# Power_Supply.net
KiCad netlist of a schematic drawn in Altium Designer
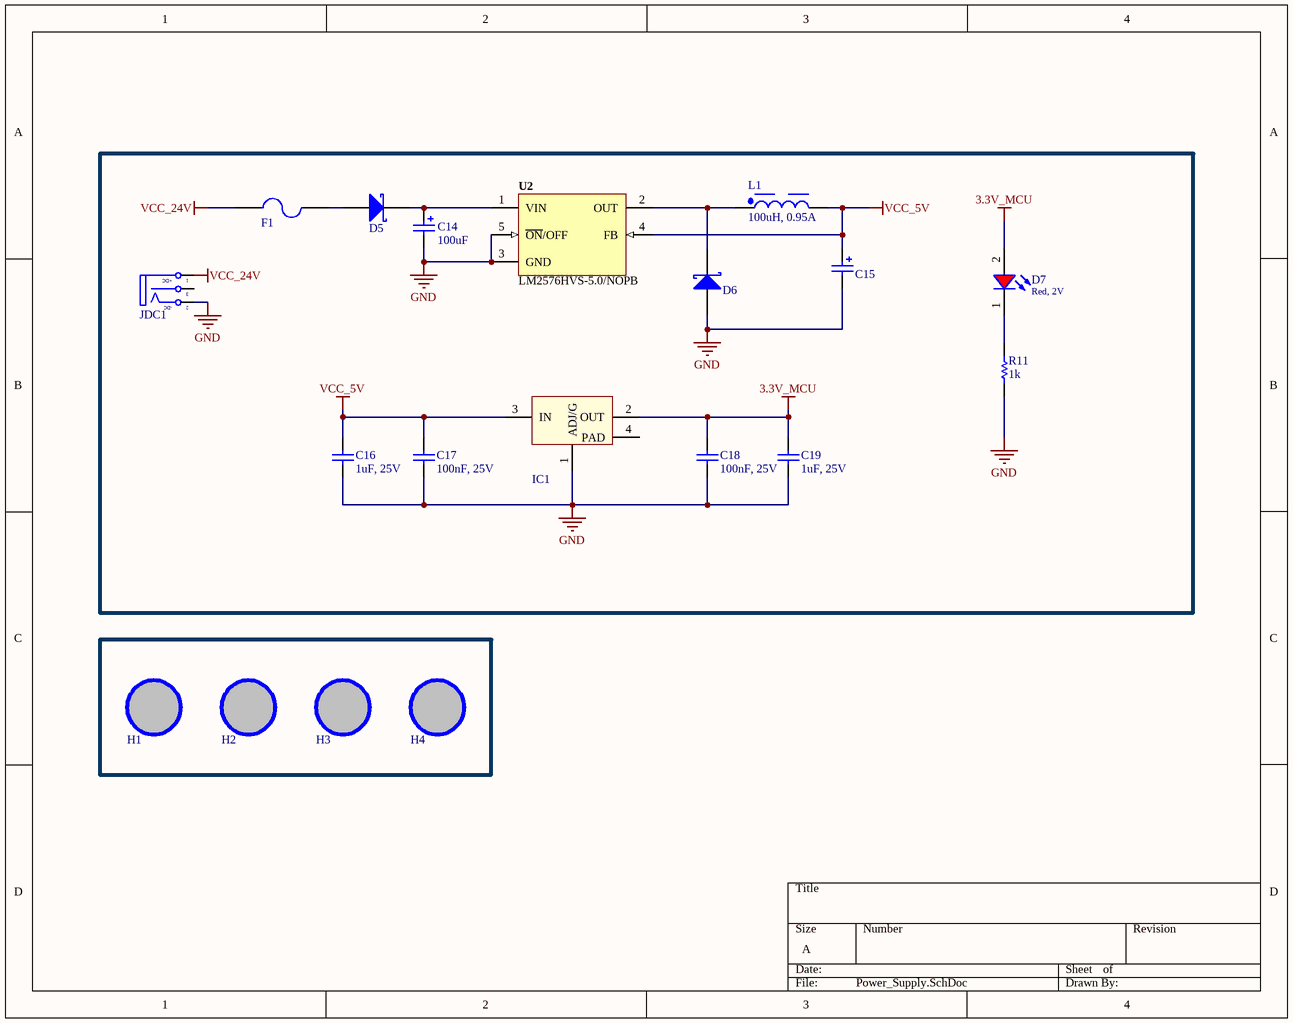
[diagram p0: Power_Supply.SchDoc]

(export (version "E")
  (design (tool "Eeschema 10.0.6"))
  (components
    (comp (ref "C14")
      (value "100uF")
      (footprint "WCAP-ATG8_D8H11.5")
      (description "WCAP-ATG8 Aluminum Electrolytic Capacitor, Radial THT, D8xH11.5mm, 100uF, 50V")
      (fields
        (field (name "MANUFACTURER") "Wurth Elektronik")
        (field (name "MANUFACTURER PART NUMBER") "860010674014")
      )
      (libsource (lib "Altium_WCAP-ATG8 (rev22a)") (part "860010674014"))
    )
    (comp (ref "C15")
      (value "1000uF")
      (footprint "WCAP-ATG8_D13H25")
      (description "WCAP-ATG8 Aluminum Electrolytic Capacitor, Radial THT, D13xH25mm, 1000uF, 50V")
      (fields
        (field (name "MANUFACTURER") "Wurth Elektronik")
        (field (name "MANUFACTURER PART NUMBER") "860010678024")
      )
      (libsource (lib "Altium_WCAP-ATG8 (rev22a)") (part "860010678024"))
    )
    (comp (ref "C16")
      (value "1uF, 25V")
      (footprint "WCAP-CSGP_0603_H=0.8mm_Reflow")
      (description "WCAP-CSGP Multilayer Ceramic Chip Capacitor, General Purpose, size 0603, X5R, 1uF, 25V")
      (fields
        (field (name "MANUFACTURER PART NUMBER") "885012106022")
        (field (name "MANUFACTURER") "Wurth Elektronik")
      )
      (libsource (lib "Altium_WCAP-CSGP (rev20a)") (part "885012106022"))
    )
    (comp (ref "C17")
      (value "100nF, 25V")
      (footprint "WCAP-CSGP_0603_H=0.8mm_Reflow")
      (description "WCAP-CSGP Multilayer Ceramic Chip Capacitor, General Purpose, size 0603, X7R, 100nF, 25V")
      (fields
        (field (name "MANUFACTURER PART NUMBER") "885012206071")
        (field (name "MANUFACTURER") "Wurth Elektronik")
      )
      (libsource (lib "Altium_WCAP-CSGP (rev20a)") (part "885012206071"))
    )
    (comp (ref "C18")
      (value "100nF, 25V")
      (footprint "WCAP-CSGP_0603_H=0.8mm_Reflow")
      (description "WCAP-CSGP Multilayer Ceramic Chip Capacitor, General Purpose, size 0603, X7R, 100nF, 25V")
      (fields
        (field (name "MANUFACTURER PART NUMBER") "885012206071")
        (field (name "MANUFACTURER") "Wurth Elektronik")
      )
      (libsource (lib "Altium_WCAP-CSGP (rev20a)") (part "885012206071"))
    )
    (comp (ref "C19")
      (value "1uF, 25V")
      (footprint "WCAP-CSGP_0603_H=0.8mm_Reflow")
      (description "WCAP-CSGP Multilayer Ceramic Chip Capacitor, General Purpose, size 0603, X5R, 1uF, 25V")
      (fields
        (field (name "MANUFACTURER PART NUMBER") "885012106022")
        (field (name "MANUFACTURER") "Wurth Elektronik")
      )
      (libsource (lib "Altium_WCAP-CSGP (rev20a)") (part "885012106022"))
    )
    (comp (ref "D5")
      (value "SS34")
      (footprint "SS34")
      (description "DIODE SCHOTTKY 40V 3A SMC")
      (fields (field (name "MFR") "onsemi") (field (name "PUBLISHER") "Altium Limited"))
      (libsource (lib "PIF_Library") (part "D Schottky"))
    )
    (comp (ref "D6")
      (value "SS34")
      (footprint "SS34")
      (description "DIODE SCHOTTKY 40V 3A SMC")
      (fields (field (name "MFR") "onsemi") (field (name "PUBLISHER") "Altium Limited"))
      (libsource (lib "PIF_Library") (part "D Schottky"))
    )
    (comp (ref "D7")
      (value "Red, 2V")
      (footprint "WL-SMCW_0603_H=0.7mm")
      (description "WL-SMCW SMT Mono-color Chip LED Waterclear, size 0603, Red, 2V, 140deg")
      (fields (field (name "PART NUMBER") "150060RS75000") (field (name "PUBLISHER") "Wurth Elektronik"))
      (libsource (lib "Altium_WL-SMCW (rev20a)") (part "150060RS75000"))
    )
    (comp (ref "F1")
      (value "0ZCG0150BF2C")
      (footprint "FUSE SMD")
      (description "PTC RESET FUSE 24V 1.5A 1812")
      (fields (field (name "MFR") "Bel Fuse Inc."))
      (libsource (lib "PIF_Library") (part "Fuse"))
    )
    (comp (ref "H1")
      (value "Hole")
      (footprint "LO KHOAN 3MM")
      (description "Hole 3mm")
      (libsource (lib "PIF_Library") (part "Hole"))
    )
    (comp (ref "H2")
      (value "Hole")
      (footprint "LO KHOAN 3MM")
      (description "Hole 3mm")
      (libsource (lib "PIF_Library") (part "Hole"))
    )
    (comp (ref "H3")
      (value "Hole")
      (footprint "LO KHOAN 3MM")
      (description "Hole 3mm")
      (libsource (lib "PIF_Library") (part "Hole"))
    )
    (comp (ref "H4")
      (value "Hole")
      (footprint "LO KHOAN 3MM")
      (description "Hole 3mm")
      (libsource (lib "PIF_Library") (part "Hole"))
    )
    (comp (ref "IC1")
      (value "LM1117IMP-3.3/NOPB")
      (footprint "SOT223-4N")
      (description "IC REG LINEAR 3.3V 800MA SOT223")
      (fields (field (name "MFR") "Texas Instruments"))
      (libsource (lib "PIF_Library") (part "LM1117"))
    )
    (comp (ref "JDC1")
      (value "G-014-4")
      (footprint "DC-IN")
      (description "DC POWER JACK, MATES TO 5.5 X 2.")
      (fields (field (name "MFR") "GlobTek, Inc."))
      (libsource (lib "PIF_Library") (part "Jack DC"))
    )
    (comp (ref "L1")
      (value "100uH, 0.95A")
      (footprint "WE-PD2SR_7850")
      (description "WE-PD2SR SMT Power Inductor, size 7850, 100uH, 0.95A, 467mOhm")
      (fields
        (field (name "MANUFACTURER") "Wurth Elektronik")
        (field (name "MANUFACTURER PART NUMBER") "744787101")
      )
      (libsource (lib "WE-PD2SR (rev22a)") (part "744787101"))
    )
    (comp (ref "R11")
      (value "1k")
      (footprint "RES-SM-0603")
      (description "RES SMD 1K OHM 5% 1/4W 0603")
      (fields (field (name "MFR") "Rohm Semiconductor") (field (name "TOLERANCE") "±5%"))
      (libsource (lib "PIF_Library") (part "RESISTOR SMD"))
    )
    (comp (ref "U2")
      (value "LM2576HVS-5.0/NOPB")
      (footprint "TO263")
      (description "IC REG BUCK 5V 3A TO263-5")
      (libsource (lib "TechMT.VN_Lib_Project v2") (part "LM2576"))
    )
  )
  (nets
    (net (code "1") (name "3.3V_MCU") (class "Default")
      (node (ref "C18") (pin "2") (pinfunction "2_2") (pintype "passive"))
      (node (ref "C19") (pin "2") (pinfunction "2_2") (pintype "passive"))
      (node (ref "D7") (pin "2") (pinfunction "A_2") (pintype "passive"))
      (node (ref "IC1") (pin "2") (pinfunction "OUT_2") (pintype "passive"))
    )
    (net (code "2") (name "GND") (class "Default")
      (node (ref "C14") (pin "2") (pinfunction "N_2") (pintype "passive"))
      (node (ref "C15") (pin "2") (pinfunction "N_2") (pintype "passive"))
      (node (ref "C16") (pin "2") (pinfunction "2_2") (pintype "passive"))
      (node (ref "C17") (pin "1") (pinfunction "1_1") (pintype "passive"))
      (node (ref "C18") (pin "1") (pinfunction "1_1") (pintype "passive"))
      (node (ref "C19") (pin "1") (pinfunction "1_1") (pintype "passive"))
      (node (ref "D6") (pin "1") (pinfunction "A_1") (pintype "passive"))
      (node (ref "IC1") (pin "1") (pinfunction "ADJ/G_1") (pintype "passive"))
      (node (ref "JDC1") (pin "2") (pinfunction "TN_2") (pintype "passive"))
      (node (ref "R11") (pin "1") (pinfunction "1_1") (pintype "passive"))
      (node (ref "U2") (pin "3") (pinfunction "GND_3") (pintype "power_in"))
      (node (ref "U2") (pin "5") (pinfunction "~{ON}/OFF_5") (pintype "input"))
    )
    (net (code "3") (name "Net-(C14-P)") (class "Default")
      (node (ref "C14") (pin "1") (pinfunction "P_1") (pintype "passive"))
      (node (ref "D5") (pin "2") (pinfunction "K_2") (pintype "passive"))
      (node (ref "U2") (pin "1") (pinfunction "VIN_1") (pintype "power_in"))
    )
    (net (code "4") (name "Net-(D5-A)") (class "Default")
      (node (ref "D5") (pin "1") (pinfunction "A_1") (pintype "passive"))
      (node (ref "F1") (pin "2") (pinfunction "2_2") (pintype "passive"))
    )
    (net (code "5") (name "Net-(D6-K)") (class "Default")
      (node (ref "D6") (pin "2") (pinfunction "K_2") (pintype "passive"))
      (node (ref "L1") (pin "1") (pinfunction "1_1") (pintype "passive"))
      (node (ref "U2") (pin "2") (pinfunction "OUT_2") (pintype "power_in"))
    )
    (net (code "6") (name "Net-(D7-K)") (class "Default")
      (node (ref "D7") (pin "1") (pinfunction "K_1") (pintype "passive"))
      (node (ref "R11") (pin "2") (pinfunction "2_2") (pintype "passive"))
    )
    (net (code "7") (name "VCC_5V") (class "Default")
      (node (ref "C15") (pin "1") (pinfunction "P_1") (pintype "passive"))
      (node (ref "C16") (pin "1") (pinfunction "1_1") (pintype "passive"))
      (node (ref "C17") (pin "2") (pinfunction "2_2") (pintype "passive"))
      (node (ref "IC1") (pin "3") (pinfunction "IN_3") (pintype "passive"))
      (node (ref "L1") (pin "2") (pinfunction "2_2") (pintype "passive"))
      (node (ref "U2") (pin "4") (pinfunction "FB_4") (pintype "input"))
    )
    (net (code "8") (name "VCC_24V") (class "Default")
      (node (ref "F1") (pin "1") (pinfunction "1_1") (pintype "passive"))
      (node (ref "JDC1") (pin "1") (pinfunction "T_1") (pintype "passive"))
    )
    (net (code "9") (name "unconnected-(H1-Pad1)") (class "Default")
      (node (ref "H1") (pin "1") (pinfunction "1_1") (pintype "passive"))
    )
    (net (code "10") (name "unconnected-(H2-Pad1)") (class "Default")
      (node (ref "H2") (pin "1") (pinfunction "1_1") (pintype "passive"))
    )
    (net (code "11") (name "unconnected-(H3-Pad1)") (class "Default")
      (node (ref "H3") (pin "1") (pinfunction "1_1") (pintype "passive"))
    )
    (net (code "12") (name "unconnected-(H4-Pad1)") (class "Default")
      (node (ref "H4") (pin "1") (pinfunction "1_1") (pintype "passive"))
    )
    (net (code "13") (name "unconnected-(IC1-PAD-Pad4)") (class "Default")
      (node (ref "IC1") (pin "4") (pinfunction "PAD_4") (pintype "passive"))
    )
    (net (code "14") (name "unconnected-(JDC1-S-Pad3)") (class "Default")
      (node (ref "JDC1") (pin "3") (pinfunction "S_3") (pintype "power_in"))
    )
  )
)
